# PenguinPi.net
KiCad netlist of a schematic drawn in Altium Designer
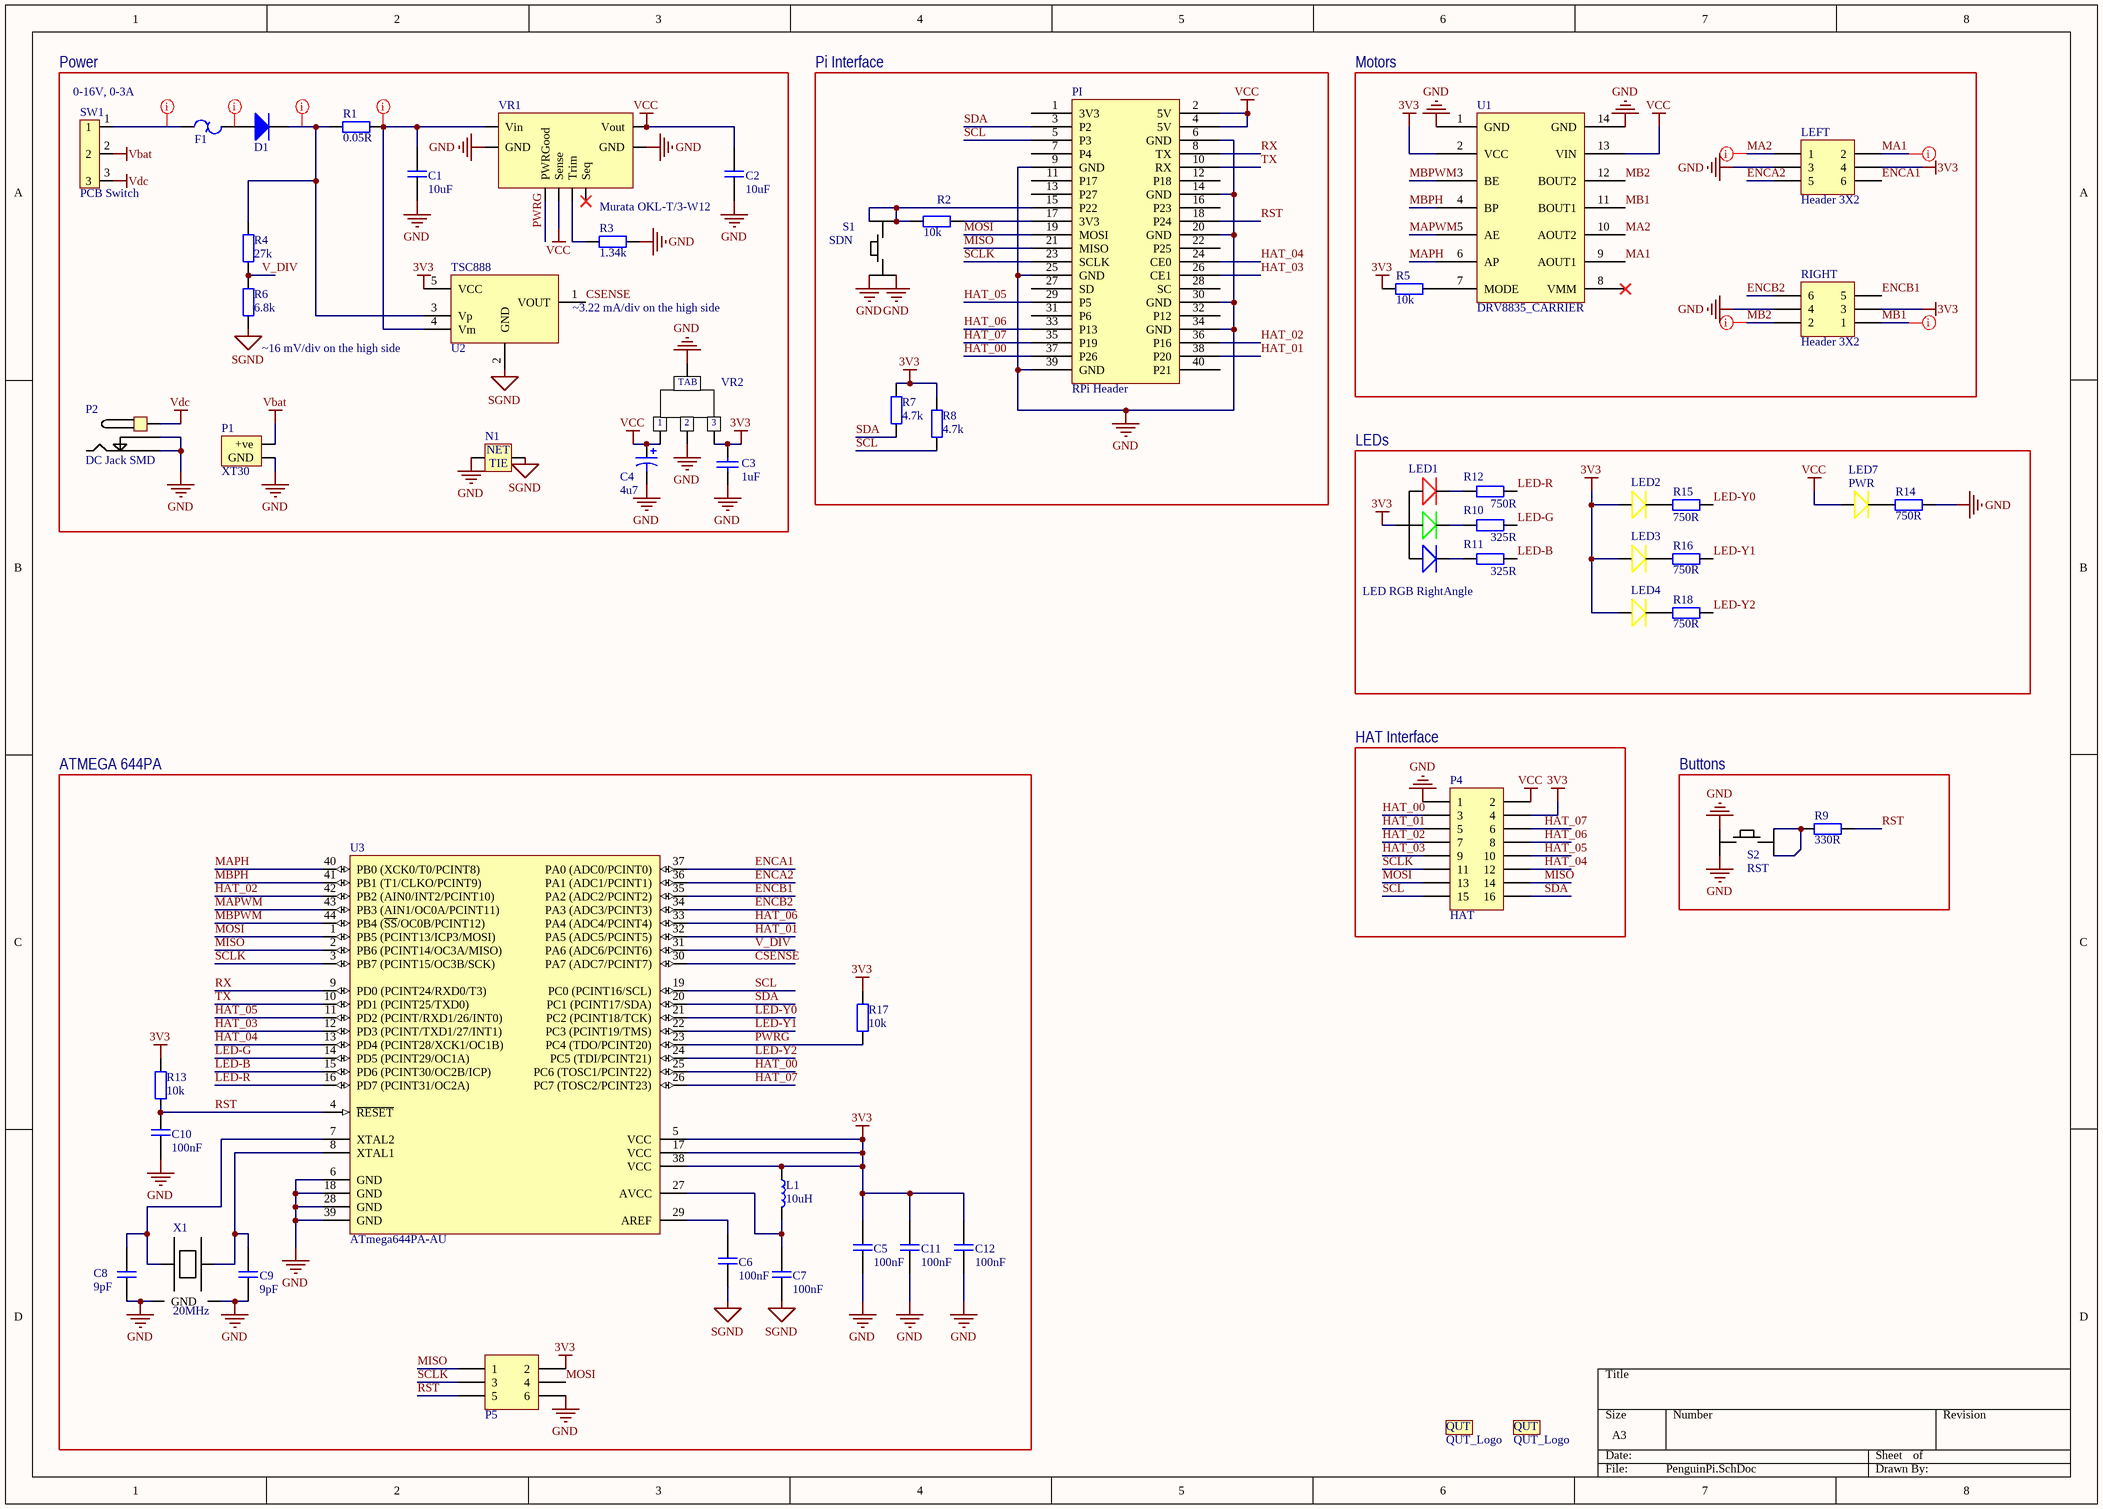
[diagram p0: PenguinPi.SchDoc]

(export (version "E")
  (design (tool "Eeschema 10.0.6"))
  (components
    (comp (ref "C1")
      (value "10uF")
      (footprint "CAPC2012X07N")
      (description "Surface mount capacitor")
      (fields (field (name "Comment") "CAP SMD"))
      (libsource (lib "Penguin") (part "CAP SMD"))
    )
    (comp (ref "C2")
      (value "10uF")
      (footprint "CAPC2012X07N")
      (description "Surface mount capacitor")
      (fields (field (name "Comment") "CAP SMD"))
      (libsource (lib "Penguin") (part "CAP SMD"))
    )
    (comp (ref "C3")
      (value "1uF")
      (footprint "6-0805_M")
      (description "Capacitor")
      (fields (field (name "Comment") "Cap") (field (name "PUBLISHER") "Altium Limited"))
      (libsource (lib "Miscellaneous Devices") (part "Cap"))
    )
    (comp (ref "C4")
      (value "4u7")
      (footprint "6-0805_M")
      (description "Polarized Capacitor (Radial)")
      (fields (field (name "Comment") "Cap Pol1") (field (name "PUBLISHER") "Altium Limited"))
      (libsource (lib "Miscellaneous Devices") (part "Cap Pol1"))
    )
    (comp (ref "C5")
      (value "100nF")
      (footprint "CAPC2012X07N")
      (description "Surface mount capacitor")
      (fields (field (name "Comment") "CAP SMD"))
      (libsource (lib "Penguin") (part "CAP SMD"))
    )
    (comp (ref "C6")
      (value "100nF")
      (footprint "CAPC2012X07N")
      (description "Surface mount capacitor")
      (fields (field (name "Comment") "CAP SMD"))
      (libsource (lib "Penguin") (part "CAP SMD"))
    )
    (comp (ref "C7")
      (value "100nF")
      (footprint "CAPC2012X07N")
      (description "Surface mount capacitor")
      (fields (field (name "Comment") "CAP SMD"))
      (libsource (lib "Penguin") (part "CAP SMD"))
    )
    (comp (ref "C8")
      (value "9pF")
      (footprint "CAPC2012X07N")
      (description "Surface mount capacitor")
      (fields (field (name "Comment") "CAP SMD"))
      (libsource (lib "Penguin") (part "CAP SMD"))
    )
    (comp (ref "C9")
      (value "9pF")
      (footprint "CAPC2012X07N")
      (description "Surface mount capacitor")
      (fields (field (name "Comment") "CAP SMD"))
      (libsource (lib "Penguin") (part "CAP SMD"))
    )
    (comp (ref "C10")
      (value "100nF")
      (footprint "CAPC2012X07N")
      (description "Surface mount capacitor")
      (fields (field (name "Comment") "CAP SMD"))
      (libsource (lib "Penguin") (part "CAP SMD"))
    )
    (comp (ref "C11")
      (value "100nF")
      (footprint "CAPC2012X07N")
      (description "Surface mount capacitor")
      (fields (field (name "Comment") "CAP SMD"))
      (libsource (lib "Penguin") (part "CAP SMD"))
    )
    (comp (ref "C12")
      (value "100nF")
      (footprint "CAPC2012X07N")
      (description "Surface mount capacitor")
      (fields (field (name "Comment") "CAP SMD"))
      (libsource (lib "Penguin") (part "CAP SMD"))
    )
    (comp (ref "D1")
      (value "SMD DIODE")
      (footprint "SODFL470X110-2N")
      (description "Surface mount Diode")
      (libsource (lib "Penguin") (part "SMD DIODE"))
    )
    (comp (ref "F1")
      (value "RGEF250")
      (footprint "MF-MSMF250/16X-2")
      (description "PPTC Thermal Fuse")
      (libsource (lib "Penguin") (part "RGEF250"))
    )
    (comp (ref "L1")
      (value "10uH")
      (footprint "CM322522")
      (description "Surface Mount Inductor - varying sizes")
      (fields (field (name "Comment") "INDUCTOR SMD"))
      (libsource (lib "Penguin") (part "INDUCTOR SMD"))
    )
    (comp (ref "LED1")
      (value "LED RGB RightAngle")
      (footprint "LED RGB RightAngle")
      (libsource (lib "PenguinPi_v2") (part "LED RGB RightAngle"))
    )
    (comp (ref "LED2")
      (value "~")
      (footprint "LED YELLOW RightAngle")
      (libsource (lib "PenguinPi_v2") (part "LED Yellow RightAngle"))
    )
    (comp (ref "LED3")
      (value "~")
      (footprint "LED YELLOW RightAngle")
      (libsource (lib "PenguinPi_v2") (part "LED Yellow RightAngle"))
    )
    (comp (ref "LED4")
      (value "~")
      (footprint "LED YELLOW RightAngle")
      (libsource (lib "PenguinPi_v2") (part "LED Yellow RightAngle"))
    )
    (comp (ref "LED7")
      (value "PWR")
      (footprint "LED YELLOW RightAngle")
      (libsource (lib "PenguinPi_v2") (part "LED Yellow RightAngle"))
    )
    (comp (ref "LEFT")
      (value "Header 3X2")
      (footprint "HDR2X3")
      (description "Header, 3-Pin, Dual row")
      (fields (field (name "PUBLISHER") "Altium Limited"))
      (libsource (lib "") (part "Header 3X2_1"))
    )
    (comp (ref "LG1") (value "QUT_Logo") (footprint "QUT_Logo") (libsource (lib "Penguin") (part "QUT_Logo")))
    (comp (ref "LG2") (value "QUT_Logo") (footprint "QUT_Logo") (libsource (lib "Penguin") (part "QUT_Logo")))
    (comp (ref "N1")
      (value "NETTIE")
      (footprint "NETTIE-SMD-5mil")
      (libsource (lib "Penguin") (part "NETTIE"))
    )
    (comp (ref "P1") (value "XT30") (footprint "XT30 - PCB mount") (libsource (lib "QUT") (part "XT30")))
    (comp (ref "P2")
      (value "DC Jack SMD")
      (footprint "DC Jack SMD")
      (libsource (lib "QUT") (part "DC Jack SMD"))
    )
    (comp (ref "P4")
      (value "HAT")
      (footprint "HDR2X8")
      (description "Header, 8-Pin, Dual row")
      (fields (field (name "PUBLISHER") "Altium Limited"))
      (libsource (lib "Miscellaneous Connectors") (part "Header 8X2"))
    )
    (comp (ref "P5")
      (value "ISP")
      (footprint "Header 3x2 nonstandard")
      (description "3 by 2 header, staggered pin arrangement")
      (libsource (lib "Penguin") (part "Header 3x2 Staggered"))
    )
    (comp (ref "PI")
      (value "RPi Header")
      (footprint "RPI 2 Header")
      (description "GPIO connector for Raspberry Pi Microcomputer")
      (libsource (lib "Penguin") (part "RPi 2 Header"))
    )
    (comp (ref "R1")
      (value "0.05R")
      (footprint "RESC3216X06M")
      (description "0805 surface mount resistor")
      (fields (field (name "Comment") "RES SMD"))
      (libsource (lib "") (part "RES SMD_3"))
    )
    (comp (ref "R2")
      (value "10k")
      (footprint "RESC2012X07N")
      (description "0805 surface mount resistor")
      (fields (field (name "Comment") "RES SMD"))
      (libsource (lib "Penguin") (part "RES SMD"))
    )
    (comp (ref "R3")
      (value "1.34k")
      (footprint "RESC2012X07N")
      (description "0805 surface mount resistor")
      (fields (field (name "Comment") "RES SMD"))
      (libsource (lib "") (part "RES SMD_2"))
    )
    (comp (ref "R4")
      (value "27k")
      (footprint "RESC2012X07N")
      (description "0805 surface mount resistor")
      (fields (field (name "Comment") "RES SMD"))
      (libsource (lib "") (part "RES SMD_1"))
    )
    (comp (ref "R5")
      (value "10k")
      (footprint "RESC2012X07N")
      (description "0805 surface mount resistor")
      (fields (field (name "Comment") "RES SMD"))
      (libsource (lib "Penguin") (part "RES SMD"))
    )
    (comp (ref "R6")
      (value "6.8k")
      (footprint "RESC2012X07N")
      (description "0805 surface mount resistor")
      (fields (field (name "Comment") "RES SMD"))
      (libsource (lib "") (part "RES SMD_1"))
    )
    (comp (ref "R7")
      (value "4.7k")
      (footprint "RESC2012X07N")
      (description "0805 surface mount resistor")
      (fields (field (name "Comment") "RES SMD"))
      (libsource (lib "") (part "RES SMD_1"))
    )
    (comp (ref "R8")
      (value "4.7k")
      (footprint "RESC2012X07N")
      (description "0805 surface mount resistor")
      (fields (field (name "Comment") "RES SMD"))
      (libsource (lib "") (part "RES SMD_1"))
    )
    (comp (ref "R9")
      (value "330R")
      (footprint "RESC2012X07N")
      (description "0805 surface mount resistor")
      (fields (field (name "Comment") "RES SMD"))
      (libsource (lib "Penguin") (part "RES SMD"))
    )
    (comp (ref "R10")
      (value "325R")
      (footprint "RESC2012X07N")
      (description "0805 surface mount resistor")
      (fields (field (name "Comment") "RES SMD"))
      (libsource (lib "Penguin") (part "RES SMD"))
    )
    (comp (ref "R11")
      (value "325R")
      (footprint "RESC2012X07N")
      (description "0805 surface mount resistor")
      (fields (field (name "Comment") "RES SMD"))
      (libsource (lib "Penguin") (part "RES SMD"))
    )
    (comp (ref "R12")
      (value "750R")
      (footprint "RESC2012X07N")
      (description "0805 surface mount resistor")
      (fields (field (name "Comment") "RES SMD"))
      (libsource (lib "Penguin") (part "RES SMD"))
    )
    (comp (ref "R13")
      (value "10k")
      (footprint "RESC2012X07N")
      (description "0805 surface mount resistor")
      (fields (field (name "Comment") "RES SMD"))
      (libsource (lib "") (part "RES SMD_1"))
    )
    (comp (ref "R14")
      (value "750R")
      (footprint "RESC2012X07N")
      (description "0805 surface mount resistor")
      (fields (field (name "Comment") "RES SMD"))
      (libsource (lib "Penguin") (part "RES SMD"))
    )
    (comp (ref "R15")
      (value "750R")
      (footprint "RESC2012X07N")
      (description "0805 surface mount resistor")
      (fields (field (name "Comment") "RES SMD"))
      (libsource (lib "Penguin") (part "RES SMD"))
    )
    (comp (ref "R16")
      (value "750R")
      (footprint "RESC2012X07N")
      (description "0805 surface mount resistor")
      (fields (field (name "Comment") "RES SMD"))
      (libsource (lib "Penguin") (part "RES SMD"))
    )
    (comp (ref "R17")
      (value "10k")
      (footprint "RESC2012X07N")
      (description "0805 surface mount resistor")
      (fields (field (name "Comment") "RES SMD"))
      (libsource (lib "") (part "RES SMD_1"))
    )
    (comp (ref "R18")
      (value "750R")
      (footprint "RESC2012X07N")
      (description "0805 surface mount resistor")
      (fields (field (name "Comment") "RES SMD"))
      (libsource (lib "Penguin") (part "RES SMD"))
    )
    (comp (ref "RIGHT")
      (value "Header 3X2")
      (footprint "HDR2X3")
      (description "Header, 3-Pin, Dual row")
      (fields (field (name "PUBLISHER") "Altium Limited"))
      (libsource (lib "Miscellaneous Connectors") (part "Header 3X2"))
    )
    (comp (ref "S1")
      (value "SDN")
      (footprint "E-SWITCH-TL3342")
      (description "TL 3342 surface mount pushbutton")
      (libsource (lib "Penguin") (part "E-SWITCH-PUSHBUTTON"))
    )
    (comp (ref "S2")
      (value "RST")
      (footprint "E-SWITCH-TL3342")
      (description "TL 3342 surface mount pushbutton")
      (libsource (lib "Penguin") (part "E-SWITCH-PUSHBUTTON"))
    )
    (comp (ref "SW1")
      (value "PCB Switch")
      (footprint "PCB Switch")
      (libsource (lib "PenguinPi_v2") (part "PCB Switch"))
    )
    (comp (ref "U1")
      (value "DRV8835_CARRIER")
      (footprint "DRV8835_CARRIER")
      (description "DRV8835 Motor Controller")
      (libsource (lib "Penguin") (part "DRV8835_CARRIER"))
    )
    (comp (ref "U2")
      (value "TSC888")
      (footprint "SOT95P280X145-5N")
      (description "Curent Sense Amplifier")
      (libsource (lib "Penguin") (part "TSC888"))
    )
    (comp (ref "U3")
      (value "ATmega644PA-AU")
      (footprint "44A_L")
      (libsource (lib "Altium Content Vault") (part "MC-8B-ATM128-SQ44"))
    )
    (comp (ref "VR1")
      (value "Murata OKL-T/3-W12")
      (footprint "OKL-T/3-W12")
      (libsource (lib "PenguinPi_v2") (part "Murata OKL-T/3-W12"))
    )
    (comp (ref "VR2") (value "FT_SOT223") (footprint "SOT233-4N") (libsource (lib "QUT") (part "FT_SOT223")))
    (comp (ref "X1") (value "20MHz") (footprint "XTAL TSX3225") (libsource (lib "QUT") (part "XTAL ABM3B")))
  )
  (nets
    (net (code "1") (name "/CSENSE") (class "Default")
      (node (ref "U2") (pin "1") (pinfunction "VOUT_1") (pintype "passive"))
      (node (ref "U3") (pin "30") (pinfunction "PA7_(ADC7/PCINT7)_30") (pintype "bidirectional"))
    )
    (net (code "2") (name "/ENCA1") (class "Default")
      (node (ref "LEFT") (pin "6") (pinfunction "6_6") (pintype "passive"))
      (node (ref "U3") (pin "37") (pinfunction "PA0_(ADC0/PCINT0)_37") (pintype "bidirectional"))
    )
    (net (code "3") (name "/ENCA2") (class "Default")
      (node (ref "LEFT") (pin "5") (pinfunction "5_5") (pintype "passive"))
      (node (ref "U3") (pin "36") (pinfunction "PA1_(ADC1/PCINT1)_36") (pintype "bidirectional"))
    )
    (net (code "4") (name "/ENCB1") (class "Default")
      (node (ref "RIGHT") (pin "5") (pinfunction "5_5") (pintype "passive"))
      (node (ref "U3") (pin "35") (pinfunction "PA2_(ADC2/PCINT2)_35") (pintype "bidirectional"))
    )
    (net (code "5") (name "/ENCB2") (class "Default")
      (node (ref "RIGHT") (pin "6") (pinfunction "6_6") (pintype "passive"))
      (node (ref "U3") (pin "34") (pinfunction "PA3_(ADC3/PCINT3)_34") (pintype "bidirectional"))
    )
    (net (code "6") (name "/HAT_00") (class "Default")
      (node (ref "P4") (pin "3") (pinfunction "3_3") (pintype "passive"))
      (node (ref "PI") (pin "37") (pinfunction "P26_37") (pintype "passive"))
      (node (ref "U3") (pin "25") (pinfunction "PC6_(TOSC1/PCINT22)_25") (pintype "bidirectional"))
    )
    (net (code "7") (name "/HAT_01") (class "Default")
      (node (ref "P4") (pin "5") (pinfunction "5_5") (pintype "passive"))
      (node (ref "PI") (pin "38") (pinfunction "P20_38") (pintype "passive"))
      (node (ref "U3") (pin "32") (pinfunction "PA5_(ADC5/PCINT5)_32") (pintype "bidirectional"))
    )
    (net (code "8") (name "/HAT_02") (class "Default")
      (node (ref "P4") (pin "7") (pinfunction "7_7") (pintype "passive"))
      (node (ref "PI") (pin "36") (pinfunction "P16_36") (pintype "passive"))
      (node (ref "U3") (pin "42") (pinfunction "PB2_(AIN0/INT2/PCINT10)_42") (pintype "bidirectional"))
    )
    (net (code "9") (name "/HAT_03") (class "Default")
      (node (ref "P4") (pin "9") (pinfunction "9_9") (pintype "passive"))
      (node (ref "PI") (pin "26") (pinfunction "CE1_26") (pintype "passive"))
      (node (ref "U3") (pin "12") (pinfunction "PD3_(PCINT/TXD1/27/INT1)_12") (pintype "bidirectional"))
    )
    (net (code "10") (name "/HAT_04") (class "Default")
      (node (ref "P4") (pin "12") (pinfunction "12_12") (pintype "passive"))
      (node (ref "PI") (pin "24") (pinfunction "CE0_24") (pintype "passive"))
      (node (ref "U3") (pin "13") (pinfunction "PD4_(PCINT28/XCK1/OC1B)_13") (pintype "bidirectional"))
    )
    (net (code "11") (name "/HAT_05") (class "Default")
      (node (ref "P4") (pin "10") (pinfunction "10_10") (pintype "passive"))
      (node (ref "PI") (pin "29") (pinfunction "P5_29") (pintype "passive"))
      (node (ref "U3") (pin "11") (pinfunction "PD2_(PCINT/RXD1/26/INT0)_11") (pintype "bidirectional"))
    )
    (net (code "12") (name "/HAT_06") (class "Default")
      (node (ref "P4") (pin "8") (pinfunction "8_8") (pintype "passive"))
      (node (ref "PI") (pin "33") (pinfunction "P13_33") (pintype "passive"))
      (node (ref "U3") (pin "33") (pinfunction "PA4_(ADC4/PCINT4)_33") (pintype "bidirectional"))
    )
    (net (code "13") (name "/HAT_07") (class "Default")
      (node (ref "P4") (pin "6") (pinfunction "6_6") (pintype "passive"))
      (node (ref "PI") (pin "35") (pinfunction "P19_35") (pintype "passive"))
      (node (ref "U3") (pin "26") (pinfunction "PC7_(TOSC2/PCINT23)_26") (pintype "bidirectional"))
    )
    (net (code "14") (name "/LED-B") (class "Default")
      (node (ref "R11") (pin "2") (pinfunction "2_2") (pintype "passive"))
      (node (ref "U3") (pin "15") (pinfunction "PD6_(PCINT30/OC2B/ICP)_15") (pintype "bidirectional"))
    )
    (net (code "15") (name "/LED-G") (class "Default")
      (node (ref "R10") (pin "2") (pinfunction "2_2") (pintype "passive"))
      (node (ref "U3") (pin "14") (pinfunction "PD5_(PCINT29/OC1A)_14") (pintype "bidirectional"))
    )
    (net (code "16") (name "/LED-R") (class "Default")
      (node (ref "R12") (pin "2") (pinfunction "2_2") (pintype "passive"))
      (node (ref "U3") (pin "16") (pinfunction "PD7_(PCINT31/OC2A)_16") (pintype "bidirectional"))
    )
    (net (code "17") (name "/LED-Y0") (class "Default")
      (node (ref "R15") (pin "2") (pinfunction "2_2") (pintype "passive"))
      (node (ref "U3") (pin "21") (pinfunction "PC2_(PCINT18/TCK)_21") (pintype "bidirectional"))
    )
    (net (code "18") (name "/LED-Y1") (class "Default")
      (node (ref "R16") (pin "2") (pinfunction "2_2") (pintype "passive"))
      (node (ref "U3") (pin "22") (pinfunction "PC3_(PCINT19/TMS)_22") (pintype "bidirectional"))
    )
    (net (code "19") (name "/LED-Y2") (class "Default")
      (node (ref "R18") (pin "2") (pinfunction "2_2") (pintype "passive"))
      (node (ref "U3") (pin "24") (pinfunction "PC5_(TDI/PCINT21)_24") (pintype "bidirectional"))
    )
    (net (code "20") (name "/MA1") (class "Default")
      (node (ref "LEFT") (pin "2") (pinfunction "2_2") (pintype "passive"))
      (node (ref "U1") (pin "9") (pinfunction "AOUT1_9") (pintype "passive"))
    )
    (net (code "21") (name "/MA2") (class "Default")
      (node (ref "LEFT") (pin "1") (pinfunction "1_1") (pintype "passive"))
      (node (ref "U1") (pin "10") (pinfunction "AOUT2_10") (pintype "passive"))
    )
    (net (code "22") (name "/MAPH") (class "Default")
      (node (ref "U1") (pin "6") (pinfunction "AP_6") (pintype "passive"))
      (node (ref "U3") (pin "40") (pinfunction "PB0_(XCK0/T0/PCINT8)_40") (pintype "bidirectional"))
    )
    (net (code "23") (name "/MAPWM") (class "Default")
      (node (ref "U1") (pin "5") (pinfunction "AE_5") (pintype "passive"))
      (node (ref "U3") (pin "43") (pinfunction "PB3_(AIN1/OC0A/PCINT11)_43") (pintype "bidirectional"))
    )
    (net (code "24") (name "/MB1") (class "Default")
      (node (ref "RIGHT") (pin "1") (pinfunction "1_1") (pintype "passive"))
      (node (ref "U1") (pin "11") (pinfunction "BOUT1_11") (pintype "passive"))
    )
    (net (code "25") (name "/MB2") (class "Default")
      (node (ref "RIGHT") (pin "2") (pinfunction "2_2") (pintype "passive"))
      (node (ref "U1") (pin "12") (pinfunction "BOUT2_12") (pintype "passive"))
    )
    (net (code "26") (name "/MBPH") (class "Default")
      (node (ref "U1") (pin "4") (pinfunction "BP_4") (pintype "passive"))
      (node (ref "U3") (pin "41") (pinfunction "PB1_(T1/CLKO/PCINT9)_41") (pintype "bidirectional"))
    )
    (net (code "27") (name "/MBPWM") (class "Default")
      (node (ref "U1") (pin "3") (pinfunction "BE_3") (pintype "passive"))
      (node (ref "U3") (pin "44") (pinfunction "PB4_(~{SS}/OC0B/PCINT12)_44") (pintype "bidirectional"))
    )
    (net (code "28") (name "/MISO") (class "Default")
      (node (ref "P4") (pin "14") (pinfunction "14_14") (pintype "passive"))
      (node (ref "P5") (pin "1") (pinfunction "1_1") (pintype "passive"))
      (node (ref "PI") (pin "21") (pinfunction "MISO_21") (pintype "passive"))
      (node (ref "U3") (pin "2") (pinfunction "PB6_(PCINT14/OC3A/MISO)_2") (pintype "bidirectional"))
    )
    (net (code "29") (name "/MOSI") (class "Default")
      (node (ref "P4") (pin "13") (pinfunction "13_13") (pintype "passive"))
      (node (ref "P5") (pin "4") (pinfunction "4_4") (pintype "passive"))
      (node (ref "PI") (pin "19") (pinfunction "MOSI_19") (pintype "passive"))
      (node (ref "U3") (pin "1") (pinfunction "PB5_(PCINT13/ICP3/MOSI)_1") (pintype "bidirectional"))
    )
    (net (code "30") (name "/PWRG") (class "Default")
      (node (ref "R17") (pin "1") (pinfunction "1_1") (pintype "passive"))
      (node (ref "U3") (pin "23") (pinfunction "PC4_(TDO/PCINT20)_23") (pintype "bidirectional"))
      (node (ref "VR1") (pin "10") (pinfunction "PWRGood_10") (pintype "passive"))
    )
    (net (code "31") (name "/RST") (class "Default")
      (node (ref "C10") (pin "2") (pinfunction "K_2") (pintype "passive"))
      (node (ref "P5") (pin "5") (pinfunction "5_5") (pintype "passive"))
      (node (ref "PI") (pin "18") (pinfunction "P24_18") (pintype "passive"))
      (node (ref "R13") (pin "1") (pinfunction "1_1") (pintype "passive"))
      (node (ref "R9") (pin "2") (pinfunction "2_2") (pintype "passive"))
      (node (ref "U3") (pin "4") (pinfunction "~{RESET}_4") (pintype "input"))
    )
    (net (code "32") (name "/RX") (class "Default")
      (node (ref "PI") (pin "8") (pinfunction "TX_8") (pintype "passive"))
      (node (ref "U3") (pin "9") (pinfunction "PD0_(PCINT24/RXD0/T3)_9") (pintype "bidirectional"))
    )
    (net (code "33") (name "/SCL") (class "Default")
      (node (ref "P4") (pin "15") (pinfunction "15_15") (pintype "passive"))
      (node (ref "PI") (pin "5") (pinfunction "P3_5") (pintype "passive"))
      (node (ref "R8") (pin "1") (pinfunction "1_1") (pintype "passive"))
      (node (ref "U3") (pin "19") (pinfunction "PC0_(PCINT16/SCL)_19") (pintype "bidirectional"))
    )
    (net (code "34") (name "/SCLK") (class "Default")
      (node (ref "P4") (pin "11") (pinfunction "11_11") (pintype "passive"))
      (node (ref "P5") (pin "3") (pinfunction "3_3") (pintype "passive"))
      (node (ref "PI") (pin "23") (pinfunction "SCLK_23") (pintype "passive"))
      (node (ref "U3") (pin "3") (pinfunction "PB7_(PCINT15/OC3B/SCK)_3") (pintype "bidirectional"))
    )
    (net (code "35") (name "/SDA") (class "Default")
      (node (ref "P4") (pin "16") (pinfunction "16_16") (pintype "passive"))
      (node (ref "PI") (pin "3") (pinfunction "P2_3") (pintype "passive"))
      (node (ref "R7") (pin "1") (pinfunction "1_1") (pintype "passive"))
      (node (ref "U3") (pin "20") (pinfunction "PC1_(PCINT17/SDA)_20") (pintype "bidirectional"))
    )
    (net (code "36") (name "/TX") (class "Default")
      (node (ref "PI") (pin "10") (pinfunction "RX_10") (pintype "passive"))
      (node (ref "U3") (pin "10") (pinfunction "PD1_(PCINT25/TXD0)_10") (pintype "bidirectional"))
    )
    (net (code "37") (name "/V_DIV") (class "Default")
      (node (ref "R4") (pin "1") (pinfunction "1_1") (pintype "passive"))
      (node (ref "R6") (pin "2") (pinfunction "2_2") (pintype "passive"))
      (node (ref "U3") (pin "31") (pinfunction "PA6_(ADC6/PCINT6)_31") (pintype "bidirectional"))
    )
    (net (code "38") (name "3V3") (class "Default")
      (node (ref "C11") (pin "2") (pinfunction "K_2") (pintype "passive"))
      (node (ref "C12") (pin "2") (pinfunction "K_2") (pintype "passive"))
      (node (ref "C3") (pin "2") (pinfunction "2_2") (pintype "passive"))
      (node (ref "C5") (pin "2") (pinfunction "K_2") (pintype "passive"))
      (node (ref "L1") (pin "1") (pinfunction "Anode_1") (pintype "passive"))
      (node (ref "LED1") (pin "2") (pinfunction "ANODE_2") (pintype "passive"))
      (node (ref "LED2") (pin "2") (pinfunction "ANODE_2") (pintype "passive"))
      (node (ref "LED3") (pin "2") (pinfunction "ANODE_2") (pintype "passive"))
      (node (ref "LED4") (pin "2") (pinfunction "ANODE_2") (pintype "passive"))
      (node (ref "LEFT") (pin "4") (pinfunction "4_4") (pintype "passive"))
      (node (ref "P4") (pin "4") (pinfunction "4_4") (pintype "passive"))
      (node (ref "P5") (pin "2") (pinfunction "2_2") (pintype "passive"))
      (node (ref "R13") (pin "2") (pinfunction "2_2") (pintype "passive"))
      (node (ref "R17") (pin "2") (pinfunction "2_2") (pintype "passive"))
      (node (ref "R5") (pin "1") (pinfunction "1_1") (pintype "passive"))
      (node (ref "R7") (pin "2") (pinfunction "2_2") (pintype "passive"))
      (node (ref "R8") (pin "2") (pinfunction "2_2") (pintype "passive"))
      (node (ref "RIGHT") (pin "3") (pinfunction "3_3") (pintype "passive"))
      (node (ref "U1") (pin "2") (pinfunction "VCC_2") (pintype "passive"))
      (node (ref "U2") (pin "5") (pinfunction "VCC_5") (pintype "passive"))
      (node (ref "U3") (pin "17") (pinfunction "VCC_17") (pintype "power_in"))
      (node (ref "U3") (pin "38") (pinfunction "VCC_38") (pintype "power_in"))
      (node (ref "U3") (pin "5") (pinfunction "VCC_5") (pintype "power_in"))
      (node (ref "VR2") (pin "3") (pinfunction "3_3") (pintype "passive"))
    )
    (net (code "39") (name "GND") (class "Default")
      (node (ref "C1") (pin "1") (pinfunction "A_1") (pintype "passive"))
      (node (ref "C10") (pin "1") (pinfunction "A_1") (pintype "passive"))
      (node (ref "C11") (pin "1") (pinfunction "A_1") (pintype "passive"))
      (node (ref "C12") (pin "1") (pinfunction "A_1") (pintype "passive"))
      (node (ref "C2") (pin "1") (pinfunction "A_1") (pintype "passive"))
      (node (ref "C3") (pin "1") (pinfunction "1_1") (pintype "passive"))
      (node (ref "C4") (pin "2") (pinfunction "2_2") (pintype "passive"))
      (node (ref "C5") (pin "1") (pinfunction "A_1") (pintype "passive"))
      (node (ref "C8") (pin "1") (pinfunction "A_1") (pintype "passive"))
      (node (ref "C9") (pin "1") (pinfunction "A_1") (pintype "passive"))
      (node (ref "LEFT") (pin "3") (pinfunction "3_3") (pintype "passive"))
      (node (ref "N1") (pin "1") (pinfunction "1_1") (pintype "passive"))
      (node (ref "P1") (pin "1") (pinfunction "GND_1") (pintype "passive"))
      (node (ref "P2") (pin "2") (pinfunction "2_2") (pintype "passive"))
      (node (ref "P2") (pin "3") (pinfunction "3_3") (pintype "passive"))
      (node (ref "P4") (pin "1") (pinfunction "1_1") (pintype "passive"))
      (node (ref "P5") (pin "6") (pinfunction "6_6") (pintype "passive"))
      (node (ref "PI") (pin "14") (pinfunction "GND_14") (pintype "passive"))
      (node (ref "PI") (pin "20") (pinfunction "GND_20") (pintype "passive"))
      (node (ref "PI") (pin "25") (pinfunction "GND_25") (pintype "passive"))
      (node (ref "PI") (pin "30") (pinfunction "GND_30") (pintype "passive"))
      (node (ref "PI") (pin "34") (pinfunction "GND_34") (pintype "passive"))
      (node (ref "PI") (pin "39") (pinfunction "GND_39") (pintype "passive"))
      (node (ref "PI") (pin "6") (pinfunction "GND_6") (pintype "passive"))
      (node (ref "PI") (pin "9") (pinfunction "GND_9") (pintype "passive"))
      (node (ref "R14") (pin "2") (pinfunction "2_2") (pintype "passive"))
      (node (ref "R3") (pin "1") (pinfunction "1_1") (pintype "passive"))
      (node (ref "RIGHT") (pin "4") (pinfunction "4_4") (pintype "passive"))
      (node (ref "S1") (pin "3") (pinfunction "B'_3") (pintype "passive"))
      (node (ref "S1") (pin "4") (pinfunction "B_4") (pintype "passive"))
      (node (ref "S2") (pin "1") (pinfunction "A_1") (pintype "passive"))
      (node (ref "S2") (pin "2") (pinfunction "A'_2") (pintype "passive"))
      (node (ref "U1") (pin "1") (pinfunction "GND_1") (pintype "passive"))
      (node (ref "U1") (pin "14") (pinfunction "GND_14") (pintype "passive"))
      (node (ref "U3") (pin "18") (pinfunction "GND_18") (pintype "power_in"))
      (node (ref "U3") (pin "28") (pinfunction "GND_28") (pintype "power_in"))
      (node (ref "U3") (pin "39") (pinfunction "GND_39") (pintype "power_in"))
      (node (ref "U3") (pin "6") (pinfunction "GND_6") (pintype "power_in"))
      (node (ref "VR1") (pin "3") (pinfunction "GND_3") (pintype "passive"))
      (node (ref "VR1") (pin "7") (pinfunction "GND_7") (pintype "passive"))
      (node (ref "VR2") (pin "2") (pinfunction "2_2") (pintype "passive"))
      (node (ref "VR2") (pin "4") (pinfunction "4_4") (pintype "passive"))
      (node (ref "X1") (pin "2") (pinfunction "GND_2") (pintype "passive"))
      (node (ref "X1") (pin "4") (pinfunction "GND_4") (pintype "passive"))
    )
    (net (code "40") (name "Net-(C1-K)") (class "Default")
      (node (ref "C1") (pin "2") (pinfunction "K_2") (pintype "passive"))
      (node (ref "R1") (pin "2") (pinfunction "2_2") (pintype "power_in"))
      (node (ref "U2") (pin "4") (pinfunction "Vm_4") (pintype "passive"))
      (node (ref "VR1") (pin "2") (pinfunction "Vin_2") (pintype "passive"))
    )
    (net (code "41") (name "Net-(C6-K)") (class "Default")
      (node (ref "C6") (pin "2") (pinfunction "K_2") (pintype "passive"))
      (node (ref "U3") (pin "29") (pinfunction "AREF_29") (pintype "power_in"))
    )
    (net (code "42") (name "Net-(C7-K)") (class "Default")
      (node (ref "C7") (pin "2") (pinfunction "K_2") (pintype "passive"))
      (node (ref "L1") (pin "2") (pinfunction "Cathode_2") (pintype "passive"))
      (node (ref "U3") (pin "27") (pinfunction "AVCC_27") (pintype "power_in"))
    )
    (net (code "43") (name "Net-(C8-K)") (class "Default")
      (node (ref "C8") (pin "2") (pinfunction "K_2") (pintype "passive"))
      (node (ref "U3") (pin "7") (pinfunction "XTAL2_7") (pintype "passive"))
      (node (ref "X1") (pin "3") (pinfunction "3_3") (pintype "passive"))
    )
    (net (code "44") (name "Net-(C9-K)") (class "Default")
      (node (ref "C9") (pin "2") (pinfunction "K_2") (pintype "passive"))
      (node (ref "U3") (pin "8") (pinfunction "XTAL1_8") (pintype "passive"))
      (node (ref "X1") (pin "1") (pinfunction "1_1") (pintype "passive"))
    )
    (net (code "45") (name "Net-(D1-Pad1)") (class "Default")
      (node (ref "D1") (pin "1") (pinfunction "1_1") (pintype "power_in"))
      (node (ref "F1") (pin "2") (pinfunction "2_2") (pintype "power_in"))
    )
    (net (code "46") (name "Net-(F1-Pad1)") (class "Default")
      (node (ref "F1") (pin "1") (pinfunction "1_1") (pintype "power_in"))
      (node (ref "SW1") (pin "1") (pinfunction "1_1") (pintype "passive"))
    )
    (net (code "47") (name "Net-(LED1-BLUE)") (class "Default")
      (node (ref "LED1") (pin "4") (pinfunction "BLUE_4") (pintype "passive"))
      (node (ref "R11") (pin "1") (pinfunction "1_1") (pintype "passive"))
    )
    (net (code "48") (name "Net-(LED1-GREEN)") (class "Default")
      (node (ref "LED1") (pin "3") (pinfunction "GREEN_3") (pintype "passive"))
      (node (ref "R10") (pin "1") (pinfunction "1_1") (pintype "passive"))
    )
    (net (code "49") (name "Net-(LED1-RED)") (class "Default")
      (node (ref "LED1") (pin "1") (pinfunction "RED_1") (pintype "passive"))
      (node (ref "R12") (pin "1") (pinfunction "1_1") (pintype "passive"))
    )
    (net (code "50") (name "Net-(LED2-YELLOW)") (class "Default")
      (node (ref "LED2") (pin "1") (pinfunction "YELLOW_1") (pintype "passive"))
      (node (ref "R15") (pin "1") (pinfunction "1_1") (pintype "passive"))
    )
    (net (code "51") (name "Net-(LED3-YELLOW)") (class "Default")
      (node (ref "LED3") (pin "1") (pinfunction "YELLOW_1") (pintype "passive"))
      (node (ref "R16") (pin "1") (pinfunction "1_1") (pintype "passive"))
    )
    (net (code "52") (name "Net-(LED4-YELLOW)") (class "Default")
      (node (ref "LED4") (pin "1") (pinfunction "YELLOW_1") (pintype "passive"))
      (node (ref "R18") (pin "1") (pinfunction "1_1") (pintype "passive"))
    )
    (net (code "53") (name "Net-(LED7-YELLOW)") (class "Default")
      (node (ref "LED7") (pin "1") (pinfunction "YELLOW_1") (pintype "passive"))
      (node (ref "R14") (pin "1") (pinfunction "1_1") (pintype "passive"))
    )
    (net (code "54") (name "Net-(PI-3V3-Pad17)") (class "Default")
      (node (ref "PI") (pin "17") (pinfunction "3V3_17") (pintype "passive"))
      (node (ref "R2") (pin "2") (pinfunction "2_2") (pintype "passive"))
    )
    (net (code "55") (name "Net-(PI-P22)") (class "Default")
      (node (ref "PI") (pin "15") (pinfunction "P22_15") (pintype "passive"))
      (node (ref "R2") (pin "1") (pinfunction "1_1") (pintype "passive"))
      (node (ref "S1") (pin "1") (pinfunction "A_1") (pintype "passive"))
      (node (ref "S1") (pin "2") (pinfunction "A'_2") (pintype "passive"))
    )
    (net (code "56") (name "Net-(S2-B')") (class "Default")
      (node (ref "R9") (pin "1") (pinfunction "1_1") (pintype "passive"))
      (node (ref "S2") (pin "3") (pinfunction "B'_3") (pintype "passive"))
      (node (ref "S2") (pin "4") (pinfunction "B_4") (pintype "passive"))
    )
    (net (code "57") (name "Net-(U1-MODE)") (class "Default")
      (node (ref "R5") (pin "2") (pinfunction "2_2") (pintype "passive"))
      (node (ref "U1") (pin "7") (pinfunction "MODE_7") (pintype "passive"))
    )
    (net (code "58") (name "Net-(U2-Vp)") (class "Default")
      (node (ref "D1") (pin "2") (pinfunction "2_2") (pintype "power_in"))
      (node (ref "R1") (pin "1") (pinfunction "1_1") (pintype "power_in"))
      (node (ref "R4") (pin "2") (pinfunction "2_2") (pintype "passive"))
      (node (ref "U2") (pin "3") (pinfunction "Vp_3") (pintype "passive"))
    )
    (net (code "59") (name "Net-(VR1-Trim)") (class "Default")
      (node (ref "R3") (pin "2") (pinfunction "2_2") (pintype "passive"))
      (node (ref "VR1") (pin "6") (pinfunction "Trim_6") (pintype "passive"))
    )
    (net (code "60") (name "SGND") (class "Default")
      (node (ref "C6") (pin "1") (pinfunction "A_1") (pintype "passive"))
      (node (ref "C7") (pin "1") (pinfunction "A_1") (pintype "passive"))
      (node (ref "N1") (pin "2") (pinfunction "2_2") (pintype "passive"))
      (node (ref "R6") (pin "1") (pinfunction "1_1") (pintype "passive"))
      (node (ref "U2") (pin "2") (pinfunction "GND_2") (pintype "passive"))
    )
    (net (code "61") (name "VCC") (class "Default")
      (node (ref "C2") (pin "2") (pinfunction "K_2") (pintype "passive"))
      (node (ref "C4") (pin "1") (pinfunction "1_1") (pintype "passive"))
      (node (ref "LED7") (pin "2") (pinfunction "ANODE_2") (pintype "passive"))
      (node (ref "P4") (pin "2") (pinfunction "2_2") (pintype "passive"))
      (node (ref "PI") (pin "2") (pinfunction "5V_2") (pintype "passive"))
      (node (ref "PI") (pin "4") (pinfunction "5V_4") (pintype "passive"))
      (node (ref "U1") (pin "13") (pinfunction "VIN_13") (pintype "passive"))
      (node (ref "VR1") (pin "4") (pinfunction "Vout_4") (pintype "passive"))
      (node (ref "VR1") (pin "5") (pinfunction "Sense_5") (pintype "passive"))
      (node (ref "VR2") (pin "1") (pinfunction "1_1") (pintype "passive"))
    )
    (net (code "62") (name "Vbat") (class "Default")
      (node (ref "P1") (pin "2") (pinfunction "+ve_2") (pintype "passive"))
      (node (ref "SW1") (pin "2") (pinfunction "2_2") (pintype "passive"))
    )
    (net (code "63") (name "Vdc") (class "Default")
      (node (ref "P2") (pin "1") (pinfunction "1_1") (pintype "passive"))
      (node (ref "SW1") (pin "3") (pinfunction "3_3") (pintype "passive"))
    )
    (net (code "64") (name "unconnected-(PI-3V3-Pad1)") (class "Default")
      (node (ref "PI") (pin "1") (pinfunction "3V3_1") (pintype "passive"))
    )
    (net (code "65") (name "unconnected-(PI-P4-Pad7)") (class "Default")
      (node (ref "PI") (pin "7") (pinfunction "P4_7") (pintype "passive"))
    )
    (net (code "66") (name "unconnected-(PI-P6-Pad31)") (class "Default")
      (node (ref "PI") (pin "31") (pinfunction "P6_31") (pintype "passive"))
    )
    (net (code "67") (name "unconnected-(PI-P12-Pad32)") (class "Default")
      (node (ref "PI") (pin "32") (pinfunction "P12_32") (pintype "passive"))
    )
    (net (code "68") (name "unconnected-(PI-P17-Pad11)") (class "Default")
      (node (ref "PI") (pin "11") (pinfunction "P17_11") (pintype "passive"))
    )
    (net (code "69") (name "unconnected-(PI-P18-Pad12)") (class "Default")
      (node (ref "PI") (pin "12") (pinfunction "P18_12") (pintype "passive"))
    )
    (net (code "70") (name "unconnected-(PI-P21-Pad40)") (class "Default")
      (node (ref "PI") (pin "40") (pinfunction "P21_40") (pintype "passive"))
    )
    (net (code "71") (name "unconnected-(PI-P23-Pad16)") (class "Default")
      (node (ref "PI") (pin "16") (pinfunction "P23_16") (pintype "passive"))
    )
    (net (code "72") (name "unconnected-(PI-P25-Pad22)") (class "Default")
      (node (ref "PI") (pin "22") (pinfunction "P25_22") (pintype "passive"))
    )
    (net (code "73") (name "unconnected-(PI-P27-Pad13)") (class "Default")
      (node (ref "PI") (pin "13") (pinfunction "P27_13") (pintype "passive"))
    )
    (net (code "74") (name "unconnected-(PI-SC-Pad28)") (class "Default")
      (node (ref "PI") (pin "28") (pinfunction "SC_28") (pintype "passive"))
    )
    (net (code "75") (name "unconnected-(PI-SD-Pad27)") (class "Default")
      (node (ref "PI") (pin "27") (pinfunction "SD_27") (pintype "passive"))
    )
    (net (code "76") (name "unconnected-(U1-VMM-Pad8)") (class "Default")
      (node (ref "U1") (pin "8") (pinfunction "VMM_8") (pintype "passive+no_connect"))
    )
    (net (code "77") (name "unconnected-(VR1-Seq-Pad9)") (class "Default")
      (node (ref "VR1") (pin "9") (pinfunction "Seq_9") (pintype "passive+no_connect"))
    )
  )
)
